# 230C_3V3_PSU_TPS40200.net
KiCad netlist of a schematic drawn in Altium Designer
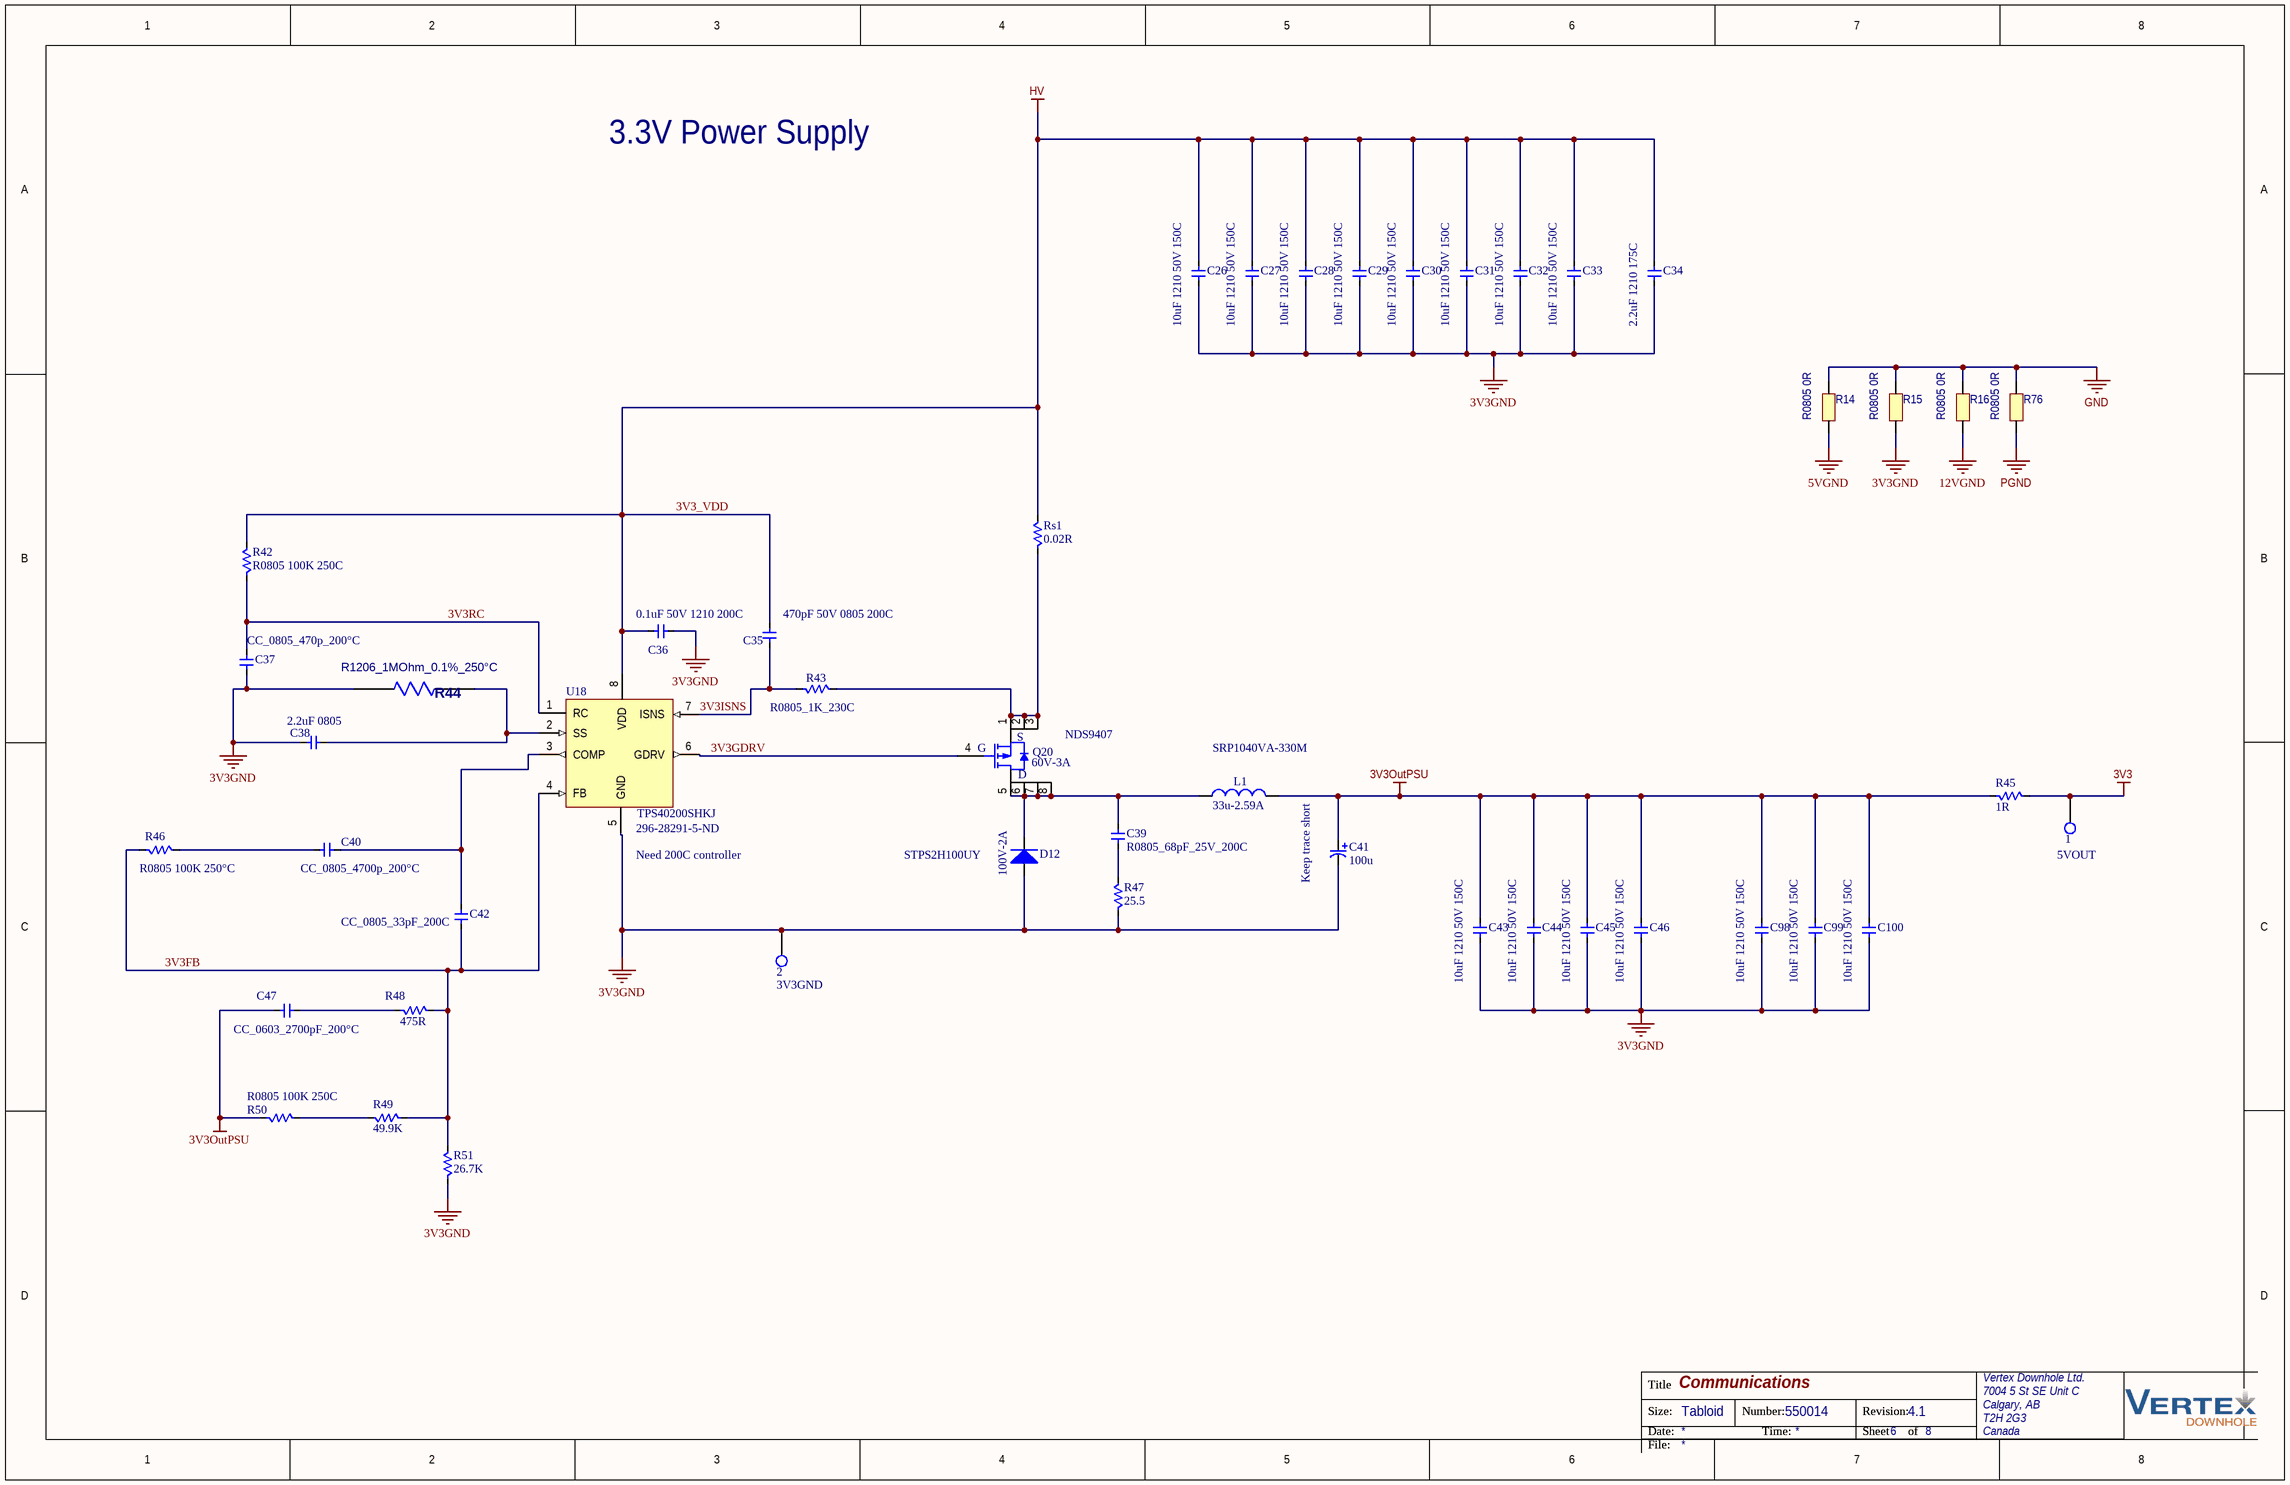
[diagram p0: 230C_3V3_PSU_TPS40200.SchDoc]

(export (version "E")
  (design (tool "Eeschema 10.0.6"))
  (components
    (comp (ref "1")
      (value "5VOUT")
      (footprint "TP-S")
      (description "Test  Point")
      (libsource (lib "Miscellaneous") (part "TP"))
    )
    (comp (ref "2")
      (value "3V3GND")
      (footprint "TP-S")
      (description "Test  Point")
      (libsource (lib "Miscellaneous") (part "TP"))
    )
    (comp (ref "C26")
      (value "10uF 1210 50V 150C")
      (footprint "1210")
      (description "CAP CER 0.1UF 50V C0G/NP0 1210 200C")
      (fields (field (name "VOLTAGE") "50V") (field (name "TOLERANCE") "±10%"))
      (libsource (lib "230C_PSU_TPS40200") (part "CC-1210"))
    )
    (comp (ref "C27")
      (value "10uF 1210 50V 150C")
      (footprint "1210")
      (description "CAP CER 0.1UF 50V C0G/NP0 1210 200C")
      (fields (field (name "VOLTAGE") "50V") (field (name "TOLERANCE") "±5%"))
      (libsource (lib "230C_PSU_TPS40200") (part "CC-1210"))
    )
    (comp (ref "C28")
      (value "10uF 1210 50V 150C")
      (footprint "1210")
      (description "CAP CER 0.1UF 50V C0G/NP0 1210 200C")
      (fields (field (name "VOLTAGE") "50V") (field (name "TOLERANCE") "±5%"))
      (libsource (lib "230C_PSU_TPS40200") (part "CC-1210"))
    )
    (comp (ref "C29")
      (value "10uF 1210 50V 150C")
      (footprint "1210")
      (description "CAP CER 0.1UF 50V C0G/NP0 1210 200C")
      (fields (field (name "VOLTAGE") "50V") (field (name "TOLERANCE") "±5%"))
      (libsource (lib "230C_PSU_TPS40200") (part "CC-1210"))
    )
    (comp (ref "C30")
      (value "10uF 1210 50V 150C")
      (footprint "1210")
      (description "CAP CER 0.1UF 50V C0G/NP0 1210 200C")
      (fields (field (name "VOLTAGE") "50V") (field (name "TOLERANCE") "±5%"))
      (libsource (lib "230C_PSU_TPS40200") (part "CC-1210"))
    )
    (comp (ref "C31")
      (value "10uF 1210 50V 150C")
      (footprint "1210")
      (description "CAP CER 0.1UF 50V C0G/NP0 1210 200C")
      (fields (field (name "VOLTAGE") "50V") (field (name "TOLERANCE") "±5%"))
      (libsource (lib "230C_PSU_TPS40200") (part "CC-1210"))
    )
    (comp (ref "C32")
      (value "10uF 1210 50V 150C")
      (footprint "1210")
      (description "CAP CER 0.1UF 50V C0G/NP0 1210 200C")
      (fields (field (name "VOLTAGE") "50V") (field (name "TOLERANCE") "±5%"))
      (libsource (lib "230C_PSU_TPS40200") (part "CC-1210"))
    )
    (comp (ref "C33")
      (value "10uF 1210 50V 150C")
      (footprint "1210")
      (description "CAP CER 0.1UF 50V C0G/NP0 1210 200C")
      (fields (field (name "VOLTAGE") "50V") (field (name "TOLERANCE") "±5%"))
      (libsource (lib "230C_PSU_TPS40200") (part "CC-1210"))
    )
    (comp (ref "C34")
      (value "2.2uF 1210 175C")
      (footprint "1210")
      (description "CAP CER 0.1UF 50V C0G/NP0 1210 200C")
      (fields (field (name "VOLTAGE") "25V") (field (name "TOLERANCE") "±5%"))
      (libsource (lib "230C_PSU_TPS40200") (part "CC-1210"))
    )
    (comp (ref "C35")
      (value "470pF 50V 0805 200C")
      (footprint "1210")
      (description "CAP CER 470PF 50V C0G/NP0 0805 200C")
      (fields (field (name "VOLTAGE") "100V") (field (name "TOLERANCE") "±5%"))
      (libsource (lib "Schlib_CES2018") (part "CC-0805-100p-100V-10%-200C-NP0"))
    )
    (comp (ref "C36")
      (value "0.1uF 50V 1210 200C")
      (footprint "0805")
      (description "CAP CER 0.1UF 50V C0G/NP0 1210 200C")
      (fields (field (name "VOLTAGE") "25V") (field (name "TOLERANCE") "±5%"))
      (libsource (lib "230C_PSU_TPS40200") (part "CC-1210"))
    )
    (comp (ref "C37")
      (value "CC_0805_470p_200°C")
      (footprint "0805")
      (description "CAPACITOR CER 470PF 100V C0G/NP0 0805")
      (fields (field (name "VOLTAGE") "100V") (field (name "TOLERANCE") "±10%"))
      (libsource (lib "Integrated_Library_CES2018") (part "CC-0805-470p-100V-10%-150C-NP0"))
    )
    (comp (ref "C38")
      (value "2.2uF 0805")
      (footprint "0805")
      (description "CAPACITOR CER 0.047UF 25V C0G/NP0 0805")
      (fields (field (name "VOLTAGE") "25V") (field (name "TOLERANCE") "±5%"))
      (libsource (lib "Integrated_Library_CES2018") (part "CC-0805-47n-25V-5%-125C-NP0"))
    )
    (comp (ref "C39")
      (value "R0805_68pF_25V_200C")
      (footprint "0805")
      (description "CAPACITOR CER 2200PF 100V C0G/NP0 0805")
      (fields (field (name "VOLTAGE") "100V") (field (name "TOLERANCE") "±5%"))
      (libsource (lib "Schlib_CES2018") (part "CC-0805-2200p-100V-5%-200C-NP0"))
    )
    (comp (ref "C40")
      (value "CC_0805_4700p_200°C")
      (footprint "0805")
      (description "CAPACITOR CER 2200PF 100V C0G/NP0 0805")
      (fields (field (name "VOLTAGE") "100V") (field (name "TOLERANCE") "±5%"))
      (libsource (lib "Schlib_CES2018") (part "CC-0805-2200p-100V-5%-200C-NP0"))
    )
    (comp (ref "C41")
      (value "100u")
      (footprint "0805")
      (description "CAPACITOR TANT 100UF 16V 10% 2917")
      (fields (field (name "VOLTAGE") "16V") (field (name "TOLERANCE") "±10%"))
      (libsource (lib "Integrated_Library_CES2018") (part "CT-2917-100u-16V-10%-150C"))
    )
    (comp (ref "C42")
      (value "CC_0805_33pF_200C")
      (footprint "1210")
      (description "CAPACITOR CER 120PF 250V NP0 0805")
      (fields (field (name "VOLTAGE") "250V") (field (name "TOLERANCE") "±5%"))
      (libsource (lib "Schlib_CES2018") (part "CC-0805-120p-100V-5%-200C-NP0"))
    )
    (comp (ref "C43")
      (value "10uF 1210 50V 150C")
      (footprint "1210")
      (description "CAP CER 0.1UF 50V C0G/NP0 1210 200C")
      (fields (field (name "VOLTAGE") "50V") (field (name "TOLERANCE") "±10%"))
      (libsource (lib "230C_PSU_TPS40200") (part "CC-1210"))
    )
    (comp (ref "C44")
      (value "10uF 1210 50V 150C")
      (footprint "1210")
      (description "CAP CER 0.1UF 50V C0G/NP0 1210 200C")
      (fields (field (name "VOLTAGE") "50V") (field (name "TOLERANCE") "±5%"))
      (libsource (lib "230C_PSU_TPS40200") (part "CC-1210"))
    )
    (comp (ref "C45")
      (value "10uF 1210 50V 150C")
      (footprint "1210")
      (description "CAP CER 0.1UF 50V C0G/NP0 1210 200C")
      (fields (field (name "VOLTAGE") "50V") (field (name "TOLERANCE") "±5%"))
      (libsource (lib "230C_PSU_TPS40200") (part "CC-1210"))
    )
    (comp (ref "C46")
      (value "10uF 1210 50V 150C")
      (footprint "1210")
      (description "CAP CER 0.1UF 50V C0G/NP0 1210 200C")
      (fields (field (name "VOLTAGE") "50V") (field (name "TOLERANCE") "±5%"))
      (libsource (lib "230C_PSU_TPS40200") (part "CC-1210"))
    )
    (comp (ref "C47")
      (value "CC_0603_2700pF_200°C")
      (footprint "0603")
      (description "CAPACITOR CER 2700PF 50V X8R 0805")
      (fields (field (name "VOLTAGE") "50V") (field (name "TOLERANCE") "±5%"))
      (libsource (lib "Integrated_Library_Greg") (part "CC-0805-2700p-50V-10%-150C"))
    )
    (comp (ref "C98")
      (value "10uF 1210 50V 150C")
      (footprint "1210")
      (description "CAP CER 0.1UF 50V C0G/NP0 1210 200C")
      (fields (field (name "VOLTAGE") "50V") (field (name "TOLERANCE") "±5%"))
      (libsource (lib "230C_PSU_TPS40200") (part "CC-1210"))
    )
    (comp (ref "C99")
      (value "10uF 1210 50V 150C")
      (footprint "1210")
      (description "CAP CER 0.1UF 50V C0G/NP0 1210 200C")
      (fields (field (name "VOLTAGE") "50V") (field (name "TOLERANCE") "±5%"))
      (libsource (lib "230C_PSU_TPS40200") (part "CC-1210"))
    )
    (comp (ref "C100")
      (value "10uF 1210 50V 150C")
      (footprint "1210")
      (description "CAP CER 0.1UF 50V C0G/NP0 1210 200C")
      (fields (field (name "VOLTAGE") "50V") (field (name "TOLERANCE") "±5%"))
      (libsource (lib "230C_PSU_TPS40200") (part "CC-1210"))
    )
    (comp (ref "D12")
      (value "100V-2A")
      (footprint "SMB")
      (description "DIODE SCHOTTKY 100V 2A SMB")
      (fields (field (name "VOLTAGE") "100V") (field (name "MFG") "STMicroelectronics"))
      (libsource (lib "Integrated_Library_CES2018") (part "DS-SMB-100V-2A"))
    )
    (comp (ref "L1")
      (value "33u-2.59A")
      (footprint "IND_CB_DRA125")
      (description "INDUCTOR 47UH 2.59A 81 MOHM")
      (fields (field (name "MFG") "Eaton") (field (name "TOLERANCE") "±20%"))
      (libsource (lib "Integrated_Library_CES2018") (part "LL-12.5X12.5-47u-2.59A"))
    )
    (comp (ref "Q20")
      (value "60V-3A")
      (footprint "SOIC_S9407_ONS")
      (description "MOSFET P-CH 60V 3A 8-SOIC")
      (fields (field (name "VOLTAGE") "60V") (field (name "MFG") "ON Semiconductor"))
      (libsource (lib "Integrated_Library_CES2018") (part "QF-SOIC8-PCH-60V-3A"))
    )
    (comp (ref "R14")
      (value "R0805 0R")
      (footprint "0805-CR")
      (description "Resistor")
      (fields (field (name "MANUFACTURER") "Yageo"))
      (libsource (lib "Resistors") (part "RES"))
    )
    (comp (ref "R15")
      (value "R0805 0R")
      (footprint "0805-CR")
      (description "Resistor")
      (fields (field (name "MANUFACTURER") "Yageo"))
      (libsource (lib "Resistors") (part "RES"))
    )
    (comp (ref "R16")
      (value "R0805 0R")
      (footprint "0805-CR")
      (description "Resistor")
      (fields (field (name "MANUFACTURER") "Yageo"))
      (libsource (lib "Resistors") (part "RES"))
    )
    (comp (ref "R42")
      (value "R0805 100K 250C")
      (footprint "0805")
      (description "100 kOhms ±0.1% 0.2W, 1/5W Chip Resistor 0805 (2012 Metric)")
      (fields (field (name "TOLERANCE") "±0.1%") (field (name "MFG") "Vishay Dale Thin Film"))
      (libsource (lib "Schlib_CES2018") (part "RS-0805-9.1K-0.1%-1/4W-155C"))
    )
    (comp (ref "R43")
      (value "R0805_1K_230C")
      (footprint "0805")
      (description "RESISTOR SMD 1K OHM 0.1% 1/8W 0805")
      (fields (field (name "TOLERANCE") "±1%") (field (name "MFG") "Vishay / Sfernice"))
      (libsource (lib "Schlib_CES2018") (part "RS-0805-1K-0.1%-1/8W-155C"))
    )
    (comp (ref "R44")
      (value "R1206_1MOhm_0.1%_250°C")
      (footprint "1206")
      (description "1206")
      (fields (field (name "MPN") "PATT1206E1004BGT1") (field (name "MFR") "Vishay Dale Thin Film"))
      (libsource (lib "BJPPS") (part "RC_1206"))
    )
    (comp (ref "R45")
      (value "1R")
      (footprint "0805")
      (description "RESISTOR SMD 1 OHM 1% 1/4W 0805")
      (fields (field (name "TOLERANCE") "±1%") (field (name "MFG") "Stackpole Electronics Inc."))
      (libsource (lib "Integrated_Library_Greg") (part "RS-0805-1R-1%-0.25W-155C"))
    )
    (comp (ref "R46")
      (value "R0805 100K 250°C")
      (footprint "0805")
      (description "100 kOhms ±0.1% 0.2W, 1/5W Chip Resistor 0805 (2012 Metric)")
      (fields (field (name "TOLERANCE") "±0.1%") (field (name "MFG") "Vishay Dale Thin Film"))
      (libsource (lib "Schlib_CES2018") (part "RS-0805-9.1K-0.1%-1/4W-155C"))
    )
    (comp (ref "R47")
      (value "25.5")
      (footprint "0805")
      (description "RESISTOR SMD 10.2K OHM 1% 1/4W 0805")
      (fields (field (name "TOLERANCE") "±1%") (field (name "MFG") "Panasonic Electronic Components"))
      (libsource (lib "Schlib_CES2018") (part "RS-0805-10.2K-0.1%-0.25W-155C"))
    )
    (comp (ref "R48")
      (value "475R")
      (footprint "0805")
      (description "RESISTOR SMD 475 OHM 0.1% 1/10W 0805")
      (fields (field (name "TOLERANCE") "±0.1%") (field (name "MFG") "Panasonic Electronic Components"))
      (libsource (lib "Schlib_CES2018") (part "RS-0805-475R-0.1%-0.25W-155C"))
    )
    (comp (ref "R49")
      (value "49.9K")
      (footprint "0805")
      (fields
        (field (name "TOLERANCE") "±0.1%")
        (field (name "MFG") "Vishay Dale Thin Film")
        (field (name "POWER") "0.250W")
      )
      (libsource (lib "Schlib_CES2018") (part "RS-0805-1.5K-0.1%-1/4W-155C"))
    )
    (comp (ref "R50")
      (value "R0805 100K 250C")
      (footprint "0805")
      (description "100 kOhms ±0.1% 0.2W, 1/5W Chip Resistor 0805 (2012 Metric)")
      (fields (field (name "TOLERANCE") "±0.1%") (field (name "MFG") "Vishay Dale Thin Film"))
      (libsource (lib "Schlib_CES2018") (part "RS-0805-9.1K-0.1%-1/4W-155C"))
    )
    (comp (ref "R51")
      (value "26.7K")
      (footprint "0805")
      (description "RESISTOR SMD 49.9 OHM 0.1% 1/25W 0805")
      (fields (field (name "TOLERANCE") "±0.1%") (field (name "MFG") "KOA Speer Electronics, Inc."))
      (libsource (lib "Schlib_CES2018") (part "RS-0805-49.9R-0.25%-0.25W-155C"))
    )
    (comp (ref "R76")
      (value "R0805 0R")
      (footprint "0805-CR")
      (description "Resistor")
      (fields (field (name "MANUFACTURER") "Yageo"))
      (libsource (lib "Resistors") (part "RES"))
    )
    (comp (ref "Rs1")
      (value "0.02R")
      (footprint "1206")
      (description "RESISTOR SMD 0.02 OHM 1% 1W 1206")
      (fields (field (name "TOLERANCE") "±1%") (field (name "MFG") "Panasonic Electronic Components"))
      (libsource (lib "Integrated_Library_CES2018") (part "RS-1206-0.02R-1%-1W-155C"))
    )
    (comp (ref "U18")
      (value "TPS40200SHKJ")
      (footprint "SOIC_S9407_ONS")
      (description "IC REG CTRLR BUCK 8CFP")
      (fields
        (field (name "MFG") "Texas Instruments")
        (field (name "SUPPLIER PART NUMBER 1") "296-28291-5-ND")
      )
      (libsource (lib "Integrated_Library_CES2018") (part "UP-SREG-CFP8-Buck-ADJ-TPS40200"))
    )
  )
  (nets
    (net (code "1") (name "/3V3FB") (class "Default")
      (node (ref "C42") (pin "1") (pinfunction "1_1") (pintype "passive"))
      (node (ref "R46") (pin "1") (pinfunction "1_1") (pintype "passive"))
      (node (ref "R48") (pin "2") (pinfunction "2_2") (pintype "passive"))
      (node (ref "R49") (pin "1") (pinfunction "1_1") (pintype "passive"))
      (node (ref "R51") (pin "2") (pinfunction "2_2") (pintype "passive"))
      (node (ref "U18") (pin "4") (pinfunction "FB_4") (pintype "input"))
    )
    (net (code "2") (name "/3V3GDRV") (class "Default")
      (node (ref "Q20") (pin "4") (pinfunction "G_4") (pintype "passive"))
      (node (ref "U18") (pin "6") (pinfunction "GDRV_6") (pintype "output"))
    )
    (net (code "3") (name "/3V3ISNS") (class "Default")
      (node (ref "C35") (pin "2") (pinfunction "2_2") (pintype "passive"))
      (node (ref "R43") (pin "1") (pinfunction "1_1") (pintype "passive"))
      (node (ref "U18") (pin "7") (pinfunction "ISNS_7") (pintype "input"))
    )
    (net (code "4") (name "/3V3RC") (class "Default")
      (node (ref "C37") (pin "2") (pinfunction "2_2") (pintype "passive"))
      (node (ref "R42") (pin "1") (pinfunction "1_1") (pintype "passive"))
      (node (ref "U18") (pin "1") (pinfunction "RC_1") (pintype "passive"))
    )
    (net (code "5") (name "3V3") (class "Default")
      (node (ref "1") (pin "1") (pinfunction "1_1") (pintype "passive"))
      (node (ref "R45") (pin "2") (pinfunction "2_2") (pintype "passive"))
    )
    (net (code "6") (name "3V3GND") (class "Default")
      (node (ref "2") (pin "1") (pinfunction "1_1") (pintype "passive"))
      (node (ref "C100") (pin "1") (pinfunction "1_1") (pintype "passive"))
      (node (ref "C26") (pin "1") (pinfunction "1_1") (pintype "passive"))
      (node (ref "C27") (pin "1") (pinfunction "1_1") (pintype "passive"))
      (node (ref "C28") (pin "1") (pinfunction "1_1") (pintype "passive"))
      (node (ref "C29") (pin "1") (pinfunction "1_1") (pintype "passive"))
      (node (ref "C30") (pin "1") (pinfunction "1_1") (pintype "passive"))
      (node (ref "C31") (pin "1") (pinfunction "1_1") (pintype "passive"))
      (node (ref "C32") (pin "1") (pinfunction "1_1") (pintype "passive"))
      (node (ref "C33") (pin "1") (pinfunction "1_1") (pintype "passive"))
      (node (ref "C34") (pin "1") (pinfunction "1_1") (pintype "passive"))
      (node (ref "C36") (pin "2") (pinfunction "2_2") (pintype "passive"))
      (node (ref "C37") (pin "1") (pinfunction "1_1") (pintype "passive"))
      (node (ref "C38") (pin "1") (pinfunction "1_1") (pintype "passive"))
      (node (ref "C41") (pin "2") (pinfunction "2_2") (pintype "passive"))
      (node (ref "C43") (pin "1") (pinfunction "1_1") (pintype "passive"))
      (node (ref "C44") (pin "1") (pinfunction "1_1") (pintype "passive"))
      (node (ref "C45") (pin "1") (pinfunction "1_1") (pintype "passive"))
      (node (ref "C46") (pin "1") (pinfunction "1_1") (pintype "passive"))
      (node (ref "C98") (pin "1") (pinfunction "1_1") (pintype "passive"))
      (node (ref "C99") (pin "1") (pinfunction "1_1") (pintype "passive"))
      (node (ref "D12") (pin "A") (pinfunction "A_A") (pintype "passive"))
      (node (ref "R15") (pin "1") (pinfunction "1_1") (pintype "passive"))
      (node (ref "R44") (pin "1") (pinfunction "A_1") (pintype "passive"))
      (node (ref "R47") (pin "1") (pinfunction "1_1") (pintype "passive"))
      (node (ref "R51") (pin "1") (pinfunction "1_1") (pintype "passive"))
      (node (ref "U18") (pin "5") (pinfunction "GND_5") (pintype "passive"))
    )
    (net (code "7") (name "3V3OutPSU") (class "Default")
      (node (ref "C100") (pin "2") (pinfunction "2_2") (pintype "passive"))
      (node (ref "C41") (pin "1") (pinfunction "1_1") (pintype "passive"))
      (node (ref "C43") (pin "2") (pinfunction "2_2") (pintype "passive"))
      (node (ref "C44") (pin "2") (pinfunction "2_2") (pintype "passive"))
      (node (ref "C45") (pin "2") (pinfunction "2_2") (pintype "passive"))
      (node (ref "C46") (pin "2") (pinfunction "2_2") (pintype "passive"))
      (node (ref "C47") (pin "1") (pinfunction "1_1") (pintype "passive"))
      (node (ref "C98") (pin "2") (pinfunction "2_2") (pintype "passive"))
      (node (ref "C99") (pin "2") (pinfunction "2_2") (pintype "passive"))
      (node (ref "L1") (pin "2") (pinfunction "2_2") (pintype "passive"))
      (node (ref "R45") (pin "1") (pinfunction "1_1") (pintype "passive"))
      (node (ref "R50") (pin "1") (pinfunction "1_1") (pintype "passive"))
    )
    (net (code "8") (name "5VGND") (class "Default")
      (node (ref "R14") (pin "1") (pinfunction "1_1") (pintype "passive"))
    )
    (net (code "9") (name "12VGND") (class "Default")
      (node (ref "R16") (pin "1") (pinfunction "1_1") (pintype "passive"))
    )
    (net (code "10") (name "GND") (class "Default")
      (node (ref "R14") (pin "2") (pinfunction "2_2") (pintype "passive"))
      (node (ref "R15") (pin "2") (pinfunction "2_2") (pintype "passive"))
      (node (ref "R16") (pin "2") (pinfunction "2_2") (pintype "passive"))
      (node (ref "R76") (pin "2") (pinfunction "2_2") (pintype "passive"))
    )
    (net (code "11") (name "HV") (class "Default")
      (node (ref "C26") (pin "2") (pinfunction "2_2") (pintype "passive"))
      (node (ref "C27") (pin "2") (pinfunction "2_2") (pintype "passive"))
      (node (ref "C28") (pin "2") (pinfunction "2_2") (pintype "passive"))
      (node (ref "C29") (pin "2") (pinfunction "2_2") (pintype "passive"))
      (node (ref "C30") (pin "2") (pinfunction "2_2") (pintype "passive"))
      (node (ref "C31") (pin "2") (pinfunction "2_2") (pintype "passive"))
      (node (ref "C32") (pin "2") (pinfunction "2_2") (pintype "passive"))
      (node (ref "C33") (pin "2") (pinfunction "2_2") (pintype "passive"))
      (node (ref "C34") (pin "2") (pinfunction "2_2") (pintype "passive"))
      (node (ref "C35") (pin "1") (pinfunction "1_1") (pintype "passive"))
      (node (ref "C36") (pin "1") (pinfunction "1_1") (pintype "passive"))
      (node (ref "R42") (pin "2") (pinfunction "2_2") (pintype "passive"))
      (node (ref "Rs1") (pin "2") (pinfunction "2_2") (pintype "passive"))
      (node (ref "U18") (pin "8") (pinfunction "VDD_8") (pintype "power_in"))
    )
    (net (code "12") (name "Net-(C39-Pad1)") (class "Default")
      (node (ref "C39") (pin "1") (pinfunction "1_1") (pintype "passive"))
      (node (ref "R47") (pin "2") (pinfunction "2_2") (pintype "passive"))
    )
    (net (code "13") (name "Net-(C39-Pad2)") (class "Default")
      (node (ref "C39") (pin "2") (pinfunction "2_2") (pintype "passive"))
      (node (ref "D12") (pin "K") (pinfunction "K_K") (pintype "passive"))
      (node (ref "L1") (pin "1") (pinfunction "1_1") (pintype "passive"))
      (node (ref "Q20") (pin "5") (pinfunction "D_5") (pintype "passive"))
      (node (ref "Q20") (pin "6") (pinfunction "D_6") (pintype "passive"))
      (node (ref "Q20") (pin "7") (pinfunction "D_7") (pintype "passive"))
      (node (ref "Q20") (pin "8") (pinfunction "D_8") (pintype "passive"))
    )
    (net (code "14") (name "Net-(C40-Pad1)") (class "Default")
      (node (ref "C40") (pin "1") (pinfunction "1_1") (pintype "passive"))
      (node (ref "R46") (pin "2") (pinfunction "2_2") (pintype "passive"))
    )
    (net (code "15") (name "Net-(C47-Pad2)") (class "Default")
      (node (ref "C47") (pin "2") (pinfunction "2_2") (pintype "passive"))
      (node (ref "R48") (pin "1") (pinfunction "1_1") (pintype "passive"))
    )
    (net (code "16") (name "Net-(Q20-S-Pad1)") (class "Default")
      (node (ref "Q20") (pin "1") (pinfunction "S_1") (pintype "passive"))
      (node (ref "Q20") (pin "2") (pinfunction "S_2") (pintype "passive"))
      (node (ref "Q20") (pin "3") (pinfunction "S_3") (pintype "passive"))
      (node (ref "R43") (pin "2") (pinfunction "2_2") (pintype "passive"))
      (node (ref "Rs1") (pin "1") (pinfunction "1_1") (pintype "passive"))
    )
    (net (code "17") (name "Net-(R44-B)") (class "Default")
      (node (ref "C38") (pin "2") (pinfunction "2_2") (pintype "passive"))
      (node (ref "R44") (pin "2") (pinfunction "B_2") (pintype "passive"))
      (node (ref "U18") (pin "2") (pinfunction "SS_2") (pintype "input"))
    )
    (net (code "18") (name "Net-(R49-Pad2)") (class "Default")
      (node (ref "R49") (pin "2") (pinfunction "2_2") (pintype "passive"))
      (node (ref "R50") (pin "2") (pinfunction "2_2") (pintype "passive"))
    )
    (net (code "19") (name "Net-(U18-COMP)") (class "Default")
      (node (ref "C40") (pin "2") (pinfunction "2_2") (pintype "passive"))
      (node (ref "C42") (pin "2") (pinfunction "2_2") (pintype "passive"))
      (node (ref "U18") (pin "3") (pinfunction "COMP_3") (pintype "output"))
    )
    (net (code "20") (name "PGND") (class "Default")
      (node (ref "R76") (pin "1") (pinfunction "1_1") (pintype "passive"))
    )
  )
)
